# 07_User_Interface.net
KiCad netlist of a schematic drawn in Altium Designer
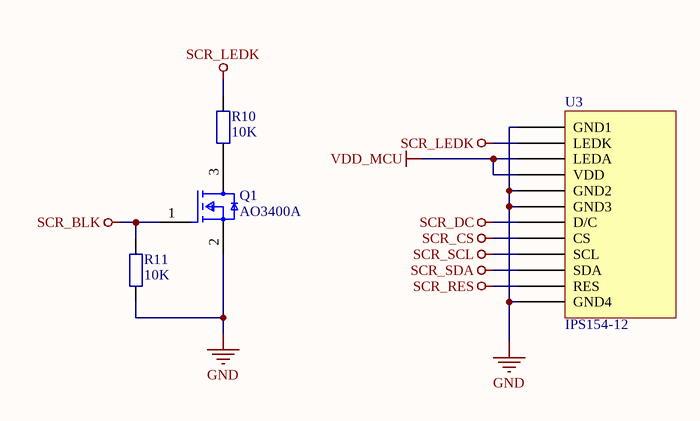
[diagram p0: [07]User Interface.SchDoc]

(export (version "E")
  (design (tool "Eeschema 10.0.6"))
  (components
    (comp (ref "Q1")
      (value "AO3400A")
      (footprint "FP-SOT23-MFG")
      (description "MOSFET N-CH 30V 5.7A SOT23")
      (libsource (lib "Altium Content Vault") (part "0a9ea7c96deaaede766a5b531c28de0"))
    )
    (comp (ref "R10")
      (value "10K")
      (footprint "RESC1005L")
      (description "Surface Mount Resistor")
      (libsource (lib "Discrete") (part "RES_CHP"))
    )
    (comp (ref "R11")
      (value "10K")
      (footprint "RESC1005L")
      (description "Surface Mount Resistor")
      (libsource (lib "Discrete") (part "RES_CHP"))
    )
    (comp (ref "U3")
      (value "IPS154-12")
      (footprint "ZJY154T-PG04 FPC 0.7mm")
      (libsource (lib "AmbiqAndromeda") (part "IPS154-12"))
    )
  )
  (nets
    (net (code "1") (name "GND") (class "Default")
      (node (ref "Q1") (pin "2") (pinfunction "S_2") (pintype "passive"))
      (node (ref "R11") (pin "2") (pinfunction "2_2") (pintype "passive"))
      (node (ref "U3") (pin "1") (pinfunction "GND1_1") (pintype "passive"))
      (node (ref "U3") (pin "12") (pinfunction "GND4_12") (pintype "passive"))
      (node (ref "U3") (pin "5") (pinfunction "GND2_5") (pintype "passive"))
      (node (ref "U3") (pin "6") (pinfunction "GND3_6") (pintype "passive"))
    )
    (net (code "2") (name "Net-(Q1-D)") (class "Default")
      (node (ref "Q1") (pin "3") (pinfunction "D_3") (pintype "passive"))
      (node (ref "R10") (pin "2") (pinfunction "2_2") (pintype "passive"))
    )
    (net (code "3") (name "SCR_BLK") (class "Default")
      (node (ref "Q1") (pin "1") (pinfunction "G_1") (pintype "passive"))
      (node (ref "R11") (pin "1") (pinfunction "1_1") (pintype "passive"))
    )
    (net (code "4") (name "SCR_CS") (class "Default")
      (node (ref "U3") (pin "8") (pinfunction "CS_8") (pintype "passive"))
    )
    (net (code "5") (name "SCR_DC") (class "Default")
      (node (ref "U3") (pin "7") (pinfunction "D/C_7") (pintype "passive"))
    )
    (net (code "6") (name "SCR_LEDK") (class "Default")
      (node (ref "R10") (pin "1") (pinfunction "1_1") (pintype "passive"))
      (node (ref "U3") (pin "2") (pinfunction "LEDK_2") (pintype "passive"))
    )
    (net (code "7") (name "SCR_RES") (class "Default")
      (node (ref "U3") (pin "11") (pinfunction "RES_11") (pintype "passive"))
    )
    (net (code "8") (name "SCR_SCL") (class "Default")
      (node (ref "U3") (pin "9") (pinfunction "SCL_9") (pintype "passive"))
    )
    (net (code "9") (name "SCR_SDA") (class "Default")
      (node (ref "U3") (pin "10") (pinfunction "SDA_10") (pintype "passive"))
    )
    (net (code "10") (name "VDD_MCU") (class "Default")
      (node (ref "U3") (pin "3") (pinfunction "LEDA_3") (pintype "passive"))
      (node (ref "U3") (pin "4") (pinfunction "VDD_4") (pintype "passive"))
    )
  )
)
